# MotionerIMU.net
KiCad netlist of a schematic drawn in EAGLE
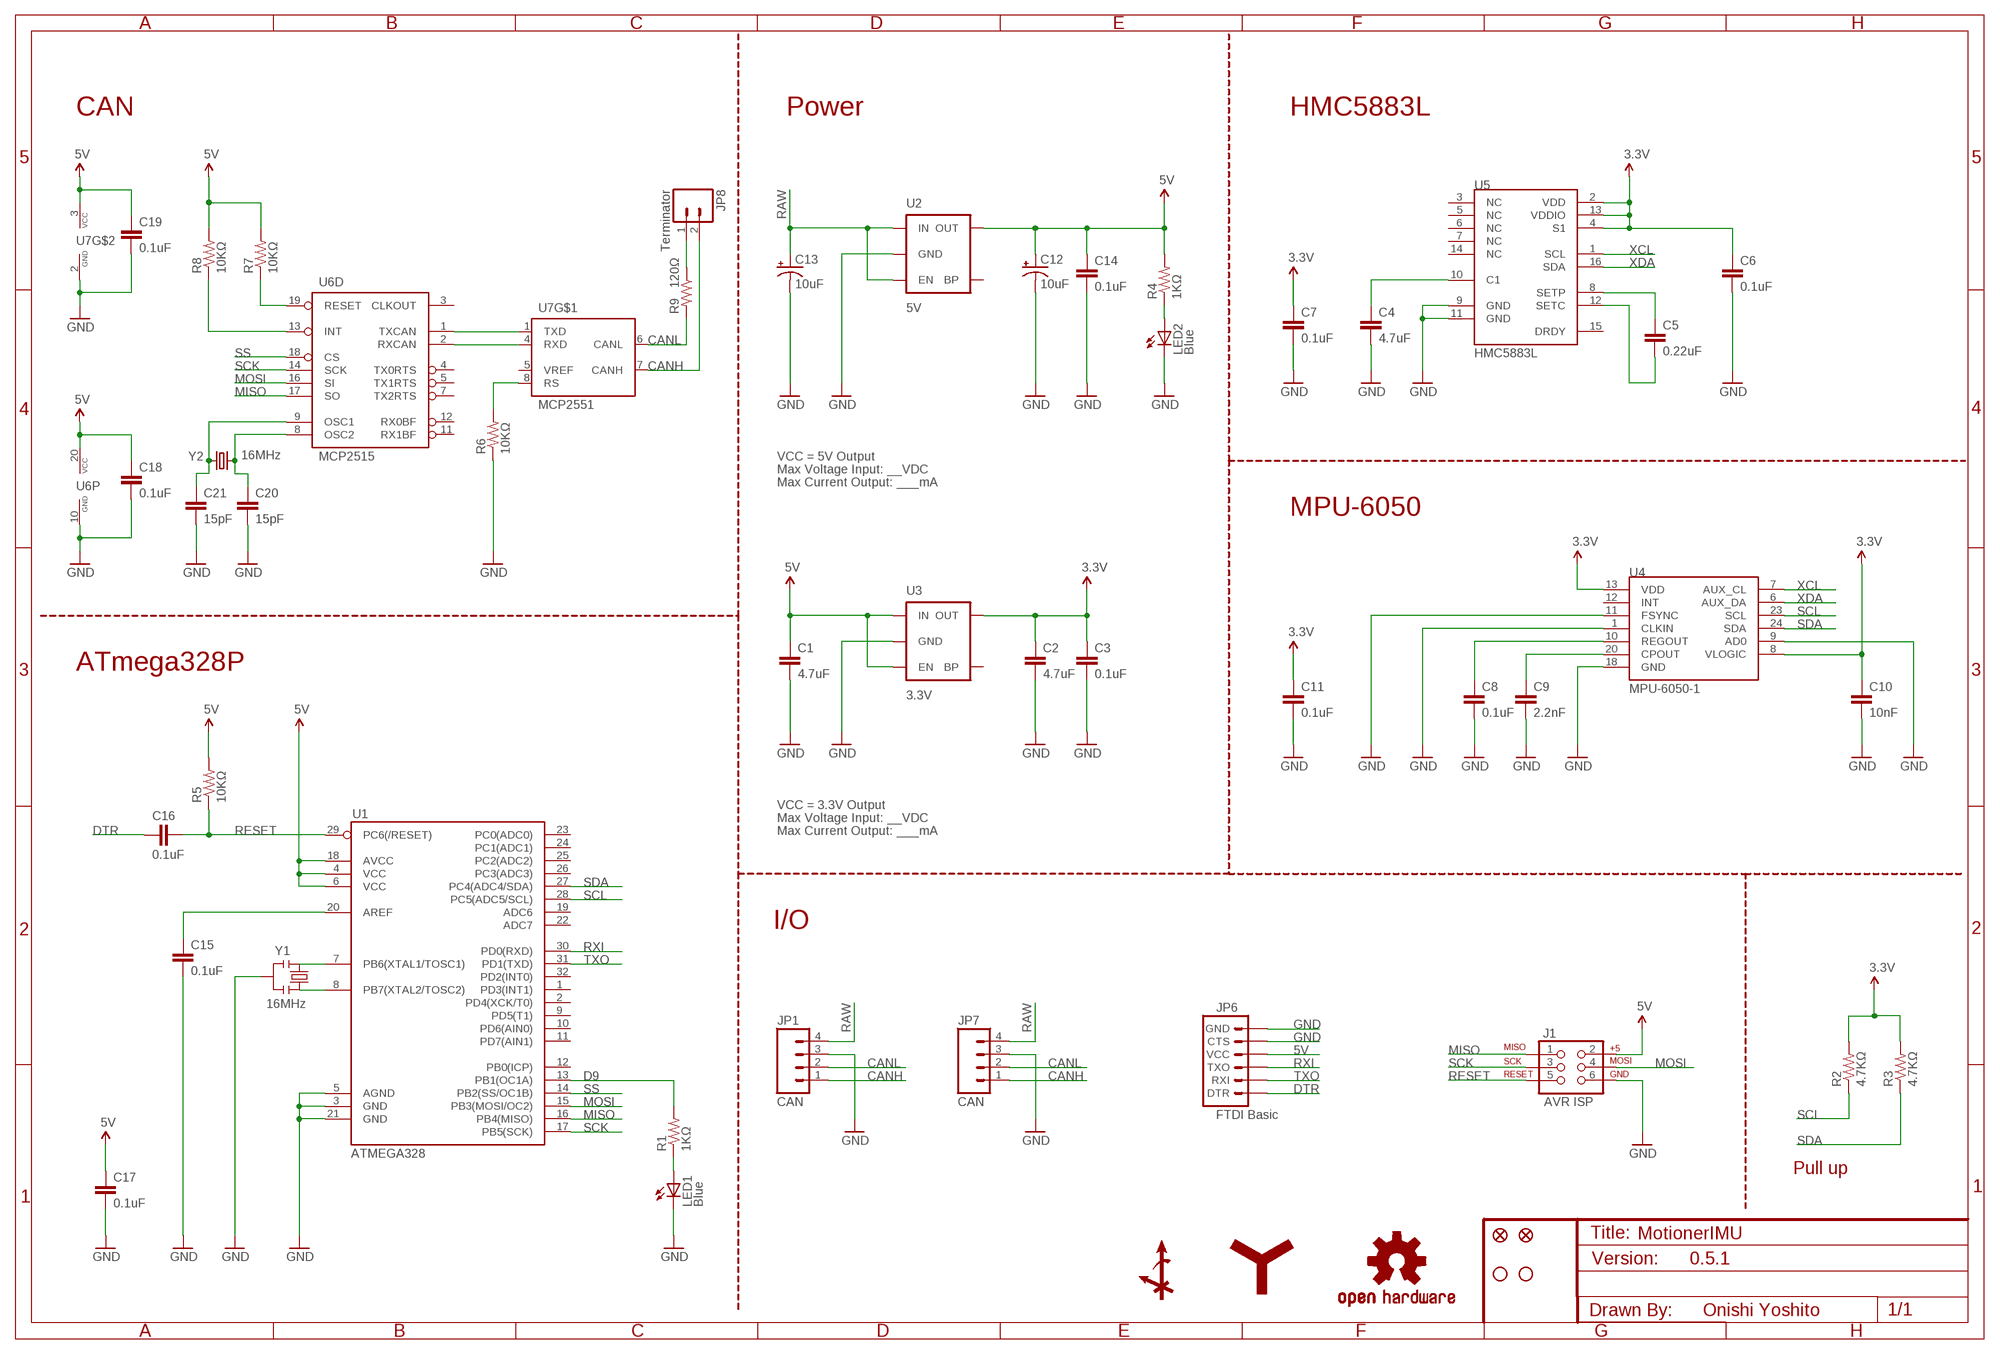
[diagram p0: schematic, sheet 1]

(export (version "E")
  (design (tool "Eeschema 10.0.6"))
  (components
    (comp (ref "C1")
      (value "4.7uF")
      (footprint "eagle-import:0402-CAP")
      (libsource (lib "eagle-import") (part "CAP0402-CAP"))
    )
    (comp (ref "C2")
      (value "4.7uF")
      (footprint "eagle-import:0402-CAP")
      (libsource (lib "eagle-import") (part "CAP0402-CAP"))
    )
    (comp (ref "C3")
      (value "0.1uF")
      (footprint "eagle-import:0402-CAP")
      (libsource (lib "eagle-import") (part "CAP0402-CAP"))
    )
    (comp (ref "C4")
      (value "4.7uF")
      (footprint "eagle-import:0402-CAP")
      (libsource (lib "eagle-import") (part "CAP0402-CAP"))
    )
    (comp (ref "C5")
      (value "0.22uF")
      (footprint "eagle-import:0402-CAP")
      (libsource (lib "eagle-import") (part "CAP0402-CAP"))
    )
    (comp (ref "C6")
      (value "0.1uF")
      (footprint "eagle-import:0402-CAP")
      (libsource (lib "eagle-import") (part "CAP0402-CAP"))
    )
    (comp (ref "C7")
      (value "0.1uF")
      (footprint "eagle-import:0402-CAP")
      (libsource (lib "eagle-import") (part "CAP0402-CAP"))
    )
    (comp (ref "C8")
      (value "0.1uF")
      (footprint "eagle-import:0402-CAP")
      (libsource (lib "eagle-import") (part "CAP0402-CAP"))
    )
    (comp (ref "C9")
      (value "2.2nF")
      (footprint "eagle-import:0402-CAP")
      (libsource (lib "eagle-import") (part "CAP0402-CAP"))
    )
    (comp (ref "C10")
      (value "10nF")
      (footprint "eagle-import:0402-CAP")
      (libsource (lib "eagle-import") (part "CAP0402-CAP"))
    )
    (comp (ref "C11")
      (value "0.1uF")
      (footprint "eagle-import:0402-CAP")
      (libsource (lib "eagle-import") (part "CAP0402-CAP"))
    )
    (comp (ref "C12")
      (value "10uF")
      (footprint "eagle-import:EIA3216")
      (libsource (lib "eagle-import") (part "CAP_POL1206"))
    )
    (comp (ref "C13")
      (value "10uF")
      (footprint "eagle-import:EIA3216")
      (libsource (lib "eagle-import") (part "CAP_POL1206"))
    )
    (comp (ref "C14")
      (value "0.1uF")
      (footprint "eagle-import:0402-CAP")
      (libsource (lib "eagle-import") (part "CAP0402-CAP"))
    )
    (comp (ref "C15")
      (value "0.1uF")
      (footprint "eagle-import:0402-CAP")
      (libsource (lib "eagle-import") (part "CAP0402-CAP"))
    )
    (comp (ref "C16")
      (value "0.1uF")
      (footprint "eagle-import:0402-CAP")
      (libsource (lib "eagle-import") (part "CAP0402-CAP"))
    )
    (comp (ref "C17")
      (value "0.1uF")
      (footprint "eagle-import:0402-CAP")
      (libsource (lib "eagle-import") (part "CAP0402-CAP"))
    )
    (comp (ref "C18")
      (value "0.1uF")
      (footprint "eagle-import:0402-CAP")
      (libsource (lib "eagle-import") (part "CAP0402-CAP"))
    )
    (comp (ref "C19")
      (value "0.1uF")
      (footprint "eagle-import:0402-CAP")
      (libsource (lib "eagle-import") (part "CAP0402-CAP"))
    )
    (comp (ref "C20")
      (value "15pF")
      (footprint "eagle-import:0402-CAP")
      (libsource (lib "eagle-import") (part "CAP0402-CAP"))
    )
    (comp (ref "C21")
      (value "15pF")
      (footprint "eagle-import:0402-CAP")
      (libsource (lib "eagle-import") (part "CAP0402-CAP"))
    )
    (comp (ref "J1")
      (value "AVR ISP")
      (footprint "eagle-import:2X3-NS")
      (libsource (lib "eagle-import") (part "AVR_SPI_PRG_6NS"))
    )
    (comp (ref "JP1")
      (value "CAN")
      (footprint "eagle-import:JST-4-PTH")
      (libsource (lib "eagle-import") (part "M04JST-PTH"))
    )
    (comp (ref "JP2")
      (value "FIDUCIALUFIDUCIAL")
      (footprint "eagle-import:MICRO-FIDUCIAL")
      (libsource (lib "eagle-import") (part "FIDUCIALUFIDUCIAL"))
    )
    (comp (ref "JP3")
      (value "STAND-OFFTIGHT")
      (footprint "eagle-import:STAND-OFF-TIGHT")
      (libsource (lib "eagle-import") (part "STAND-OFFTIGHT"))
    )
    (comp (ref "JP4")
      (value "STAND-OFFTIGHT")
      (footprint "eagle-import:STAND-OFF-TIGHT")
      (libsource (lib "eagle-import") (part "STAND-OFFTIGHT"))
    )
    (comp (ref "JP5")
      (value "FIDUCIALUFIDUCIAL")
      (footprint "eagle-import:MICRO-FIDUCIAL")
      (libsource (lib "eagle-import") (part "FIDUCIALUFIDUCIAL"))
    )
    (comp (ref "JP6")
      (value "FTDI Basic")
      (footprint "eagle-import:1X06")
      (libsource (lib "eagle-import") (part "ARDUINO_SERIAL_PROGRAMPTH"))
    )
    (comp (ref "JP7")
      (value "CAN")
      (footprint "eagle-import:JST-4-PTH")
      (libsource (lib "eagle-import") (part "M04JST-PTH"))
    )
    (comp (ref "JP8")
      (value "Terminator")
      (footprint "eagle-import:1X02")
      (libsource (lib "eagle-import") (part "M02PTH"))
    )
    (comp (ref "LED1")
      (value "Blue")
      (footprint "eagle-import:LED-0603")
      (libsource (lib "eagle-import") (part "LED0603"))
    )
    (comp (ref "LED2")
      (value "Blue")
      (footprint "eagle-import:LED-0603")
      (libsource (lib "eagle-import") (part "LED0603"))
    )
    (comp (ref "R1")
      (value "1KΩ")
      (footprint "eagle-import:0402-RES")
      (libsource (lib "eagle-import") (part "RESISTOR0402-RES"))
    )
    (comp (ref "R2")
      (value "4.7KΩ")
      (footprint "eagle-import:0402-RES")
      (libsource (lib "eagle-import") (part "RESISTOR0402-RES"))
    )
    (comp (ref "R3")
      (value "4.7KΩ")
      (footprint "eagle-import:0402-RES")
      (libsource (lib "eagle-import") (part "RESISTOR0402-RES"))
    )
    (comp (ref "R4")
      (value "1KΩ")
      (footprint "eagle-import:0402-RES")
      (libsource (lib "eagle-import") (part "RESISTOR0402-RES"))
    )
    (comp (ref "R5")
      (value "10KΩ")
      (footprint "eagle-import:0402-RES")
      (libsource (lib "eagle-import") (part "RESISTOR0402-RES"))
    )
    (comp (ref "R6")
      (value "10KΩ")
      (footprint "eagle-import:0402-RES")
      (libsource (lib "eagle-import") (part "RESISTOR0402-RES"))
    )
    (comp (ref "R7")
      (value "10KΩ")
      (footprint "eagle-import:0402-RES")
      (libsource (lib "eagle-import") (part "RESISTOR0402-RES"))
    )
    (comp (ref "R8")
      (value "10KΩ")
      (footprint "eagle-import:0402-RES")
      (libsource (lib "eagle-import") (part "RESISTOR0402-RES"))
    )
    (comp (ref "R9")
      (value "120Ω")
      (footprint "eagle-import:0402-RES")
      (libsource (lib "eagle-import") (part "RESISTOR0402-RES"))
    )
    (comp (ref "U$2")
      (value "OSHW-LOGOS")
      (footprint "eagle-import:OSHW-LOGO-S")
      (libsource (lib "eagle-import") (part "OSHW-LOGOS"))
    )
    (comp (ref "U$11")
      (value "AXIS-ANGLE_S")
      (footprint "eagle-import:AXIS-ANGLE_S")
      (libsource (lib "eagle-import") (part "AXIS-ANGLE_S"))
    )
    (comp (ref "U$13")
      (value "YCAM_LOGO_L")
      (footprint "eagle-import:YCAM_LOGO_L")
      (libsource (lib "eagle-import") (part "YCAM_LOGO_L"))
    )
    (comp (ref "U1")
      (value "ATMEGA328")
      (footprint "eagle-import:TQFP32-08")
      (libsource (lib "eagle-import") (part "ATMEGA168"))
    )
    (comp (ref "U2")
      (value "5V")
      (footprint "eagle-import:SOT23-5")
      (libsource (lib "eagle-import") (part "V_REG_LDOSMD"))
    )
    (comp (ref "U3")
      (value "3.3V")
      (footprint "eagle-import:SOT23-5")
      (libsource (lib "eagle-import") (part "V_REG_LDOSMD"))
    )
    (comp (ref "U4")
      (value "MPU-6050-1")
      (footprint "eagle-import:QFN-24-4MM2")
      (libsource (lib "eagle-import") (part "MPU-6050-1"))
    )
    (comp (ref "U5")
      (value "HMC5883L")
      (footprint "eagle-import:16LPCC")
      (libsource (lib "eagle-import") (part "HMC5883LSMD"))
    )
    (comp (ref "U6")
      (value "MCP2515")
      (footprint "eagle-import:TSSOP20")
      (libsource (lib "eagle-import") (part "MCP2515ST"))
    )
    (comp (ref "U7")
      (value "MCP2551")
      (footprint "eagle-import:SO08")
      (libsource (lib "eagle-import") (part "MCP2551SO8"))
    )
    (comp (ref "Y1")
      (value "16MHz")
      (footprint "eagle-import:RESONATOR-SMD")
      (libsource (lib "eagle-import") (part "RESONATORSMD"))
    )
    (comp (ref "Y2")
      (value "16MHz")
      (footprint "eagle-import:CRYSTAL-SMD-5X3")
      (libsource (lib "eagle-import") (part "CRYSTAL5X3"))
    )
  )
  (nets
    (net (code "1") (name "/CANH") (class "Default")
      (node (ref "JP1") (pin "1") (pinfunction "1_1") (pintype "passive"))
      (node (ref "JP7") (pin "1") (pinfunction "1_1") (pintype "passive"))
      (node (ref "JP8") (pin "2") (pinfunction "2_2") (pintype "passive"))
      (node (ref "U7") (pin "7") (pinfunction "CANH_7") (pintype "bidirectional"))
    )
    (net (code "2") (name "/CANL") (class "Default")
      (node (ref "JP1") (pin "2") (pinfunction "2_2") (pintype "passive"))
      (node (ref "JP7") (pin "2") (pinfunction "2_2") (pintype "passive"))
      (node (ref "R9") (pin "2") (pinfunction "2_2") (pintype "passive"))
      (node (ref "U7") (pin "6") (pinfunction "CANL_6") (pintype "bidirectional"))
    )
    (net (code "3") (name "/D9") (class "Default")
      (node (ref "R1") (pin "2") (pinfunction "2_2") (pintype "passive"))
      (node (ref "U1") (pin "13") (pinfunction "PB1(OC1A)_13") (pintype "bidirectional"))
    )
    (net (code "4") (name "/DTR") (class "Default")
      (node (ref "C16") (pin "1") (pinfunction "1_1") (pintype "passive"))
      (node (ref "JP6") (pin "1") (pinfunction "DTR_1") (pintype "passive"))
    )
    (net (code "5") (name "/MISO") (class "Default")
      (node (ref "J1") (pin "1") (pinfunction "1_1") (pintype "passive"))
      (node (ref "U1") (pin "16") (pinfunction "PB4(MISO)_16") (pintype "bidirectional"))
      (node (ref "U6") (pin "17") (pinfunction "SO_17") (pintype "output"))
    )
    (net (code "6") (name "/MOSI") (class "Default")
      (node (ref "J1") (pin "4") (pinfunction "4_4") (pintype "passive"))
      (node (ref "U1") (pin "15") (pinfunction "PB3(MOSI/OC2)_15") (pintype "bidirectional"))
      (node (ref "U6") (pin "16") (pinfunction "SI_16") (pintype "input"))
    )
    (net (code "7") (name "/RAW") (class "Default")
      (node (ref "C13") (pin "A") (pinfunction "+_A") (pintype "passive"))
      (node (ref "JP1") (pin "4") (pinfunction "4_4") (pintype "passive"))
      (node (ref "JP7") (pin "4") (pinfunction "4_4") (pintype "passive"))
      (node (ref "U2") (pin "1") (pinfunction "IN_1") (pintype "input"))
      (node (ref "U2") (pin "3") (pinfunction "EN_3") (pintype "input"))
    )
    (net (code "8") (name "/RESET") (class "Default")
      (node (ref "C16") (pin "2") (pinfunction "2_2") (pintype "passive"))
      (node (ref "J1") (pin "5") (pinfunction "5_5") (pintype "passive"))
      (node (ref "R5") (pin "1") (pinfunction "1_1") (pintype "passive"))
      (node (ref "U1") (pin "29") (pinfunction "PC6(/RESET)_29") (pintype "bidirectional"))
    )
    (net (code "9") (name "/RXI") (class "Default")
      (node (ref "JP6") (pin "3") (pinfunction "TXO_3") (pintype "passive"))
      (node (ref "U1") (pin "30") (pinfunction "PD0(RXD)_30") (pintype "bidirectional"))
    )
    (net (code "10") (name "/SCK") (class "Default")
      (node (ref "J1") (pin "3") (pinfunction "3_3") (pintype "passive"))
      (node (ref "U1") (pin "17") (pinfunction "PB5(SCK)_17") (pintype "bidirectional"))
      (node (ref "U6") (pin "14") (pinfunction "SCK_14") (pintype "input"))
    )
    (net (code "11") (name "/SCL") (class "Default")
      (node (ref "R2") (pin "1") (pinfunction "1_1") (pintype "passive"))
      (node (ref "U1") (pin "28") (pinfunction "PC5(ADC5/SCL)_28") (pintype "bidirectional"))
      (node (ref "U4") (pin "23") (pinfunction "SCL_23") (pintype "bidirectional"))
    )
    (net (code "12") (name "/SDA") (class "Default")
      (node (ref "R3") (pin "1") (pinfunction "1_1") (pintype "passive"))
      (node (ref "U1") (pin "27") (pinfunction "PC4(ADC4/SDA)_27") (pintype "bidirectional"))
      (node (ref "U4") (pin "24") (pinfunction "SDA_24") (pintype "bidirectional"))
    )
    (net (code "13") (name "/SS") (class "Default")
      (node (ref "U1") (pin "14") (pinfunction "PB2(SS/OC1B)_14") (pintype "bidirectional"))
      (node (ref "U6") (pin "18") (pinfunction "CS_18") (pintype "input"))
    )
    (net (code "14") (name "/TXO") (class "Default")
      (node (ref "JP6") (pin "2") (pinfunction "RXI_2") (pintype "passive"))
      (node (ref "U1") (pin "31") (pinfunction "PD1(TXD)_31") (pintype "bidirectional"))
    )
    (net (code "15") (name "/XCL") (class "Default")
      (node (ref "U4") (pin "7") (pinfunction "AUX_CL_7") (pintype "bidirectional"))
      (node (ref "U5") (pin "1") (pinfunction "SCL_1") (pintype "bidirectional"))
    )
    (net (code "16") (name "/XDA") (class "Default")
      (node (ref "U4") (pin "6") (pinfunction "AUX_DA_6") (pintype "bidirectional"))
      (node (ref "U5") (pin "16") (pinfunction "SDA_16") (pintype "bidirectional"))
    )
    (net (code "17") (name "3.3V") (class "Default")
      (node (ref "C10") (pin "1") (pinfunction "1_1") (pintype "passive"))
      (node (ref "C11") (pin "1") (pinfunction "1_1") (pintype "passive"))
      (node (ref "C2") (pin "1") (pinfunction "1_1") (pintype "passive"))
      (node (ref "C3") (pin "1") (pinfunction "1_1") (pintype "passive"))
      (node (ref "C6") (pin "1") (pinfunction "1_1") (pintype "passive"))
      (node (ref "C7") (pin "1") (pinfunction "1_1") (pintype "passive"))
      (node (ref "R2") (pin "2") (pinfunction "2_2") (pintype "passive"))
      (node (ref "R3") (pin "2") (pinfunction "2_2") (pintype "passive"))
      (node (ref "U3") (pin "5") (pinfunction "OUT_5") (pintype "passive"))
      (node (ref "U4") (pin "13") (pinfunction "VDD_13") (pintype "bidirectional"))
      (node (ref "U4") (pin "8") (pinfunction "VLOGIC_8") (pintype "bidirectional"))
      (node (ref "U5") (pin "13") (pinfunction "VDDIO_13") (pintype "bidirectional"))
      (node (ref "U5") (pin "2") (pinfunction "VDD_2") (pintype "bidirectional"))
      (node (ref "U5") (pin "4") (pinfunction "S1_4") (pintype "bidirectional"))
    )
    (net (code "18") (name "5V") (class "Default")
      (node (ref "C1") (pin "1") (pinfunction "1_1") (pintype "passive"))
      (node (ref "C12") (pin "A") (pinfunction "+_A") (pintype "passive"))
      (node (ref "C14") (pin "1") (pinfunction "1_1") (pintype "passive"))
      (node (ref "C17") (pin "1") (pinfunction "1_1") (pintype "passive"))
      (node (ref "C18") (pin "1") (pinfunction "1_1") (pintype "passive"))
      (node (ref "C19") (pin "1") (pinfunction "1_1") (pintype "passive"))
      (node (ref "J1") (pin "2") (pinfunction "2_2") (pintype "passive"))
      (node (ref "JP6") (pin "4") (pinfunction "VCC_4") (pintype "passive"))
      (node (ref "R4") (pin "2") (pinfunction "2_2") (pintype "passive"))
      (node (ref "R5") (pin "2") (pinfunction "2_2") (pintype "passive"))
      (node (ref "R7") (pin "2") (pinfunction "2_2") (pintype "passive"))
      (node (ref "R8") (pin "2") (pinfunction "2_2") (pintype "passive"))
      (node (ref "U1") (pin "18") (pinfunction "AVCC_18") (pintype "bidirectional"))
      (node (ref "U1") (pin "4") (pinfunction "VCC_4") (pintype "bidirectional"))
      (node (ref "U1") (pin "6") (pinfunction "VCC_6") (pintype "bidirectional"))
      (node (ref "U2") (pin "5") (pinfunction "OUT_5") (pintype "passive"))
      (node (ref "U3") (pin "1") (pinfunction "IN_1") (pintype "input"))
      (node (ref "U3") (pin "3") (pinfunction "EN_3") (pintype "input"))
      (node (ref "U6") (pin "20") (pinfunction "VCC_20") (pintype "power_in"))
      (node (ref "U7") (pin "3") (pinfunction "VCC_3") (pintype "power_in"))
    )
    (net (code "19") (name "GND") (class "Default")
      (node (ref "C1") (pin "2") (pinfunction "2_2") (pintype "passive"))
      (node (ref "C10") (pin "2") (pinfunction "2_2") (pintype "passive"))
      (node (ref "C11") (pin "2") (pinfunction "2_2") (pintype "passive"))
      (node (ref "C12") (pin "C") (pinfunction "-_C") (pintype "passive"))
      (node (ref "C13") (pin "C") (pinfunction "-_C") (pintype "passive"))
      (node (ref "C14") (pin "2") (pinfunction "2_2") (pintype "passive"))
      (node (ref "C15") (pin "2") (pinfunction "2_2") (pintype "passive"))
      (node (ref "C17") (pin "2") (pinfunction "2_2") (pintype "passive"))
      (node (ref "C18") (pin "2") (pinfunction "2_2") (pintype "passive"))
      (node (ref "C19") (pin "2") (pinfunction "2_2") (pintype "passive"))
      (node (ref "C2") (pin "2") (pinfunction "2_2") (pintype "passive"))
      (node (ref "C20") (pin "2") (pinfunction "2_2") (pintype "passive"))
      (node (ref "C21") (pin "2") (pinfunction "2_2") (pintype "passive"))
      (node (ref "C3") (pin "2") (pinfunction "2_2") (pintype "passive"))
      (node (ref "C4") (pin "2") (pinfunction "2_2") (pintype "passive"))
      (node (ref "C6") (pin "2") (pinfunction "2_2") (pintype "passive"))
      (node (ref "C7") (pin "2") (pinfunction "2_2") (pintype "passive"))
      (node (ref "C8") (pin "2") (pinfunction "2_2") (pintype "passive"))
      (node (ref "C9") (pin "2") (pinfunction "2_2") (pintype "passive"))
      (node (ref "J1") (pin "6") (pinfunction "6_6") (pintype "passive"))
      (node (ref "JP1") (pin "3") (pinfunction "3_3") (pintype "passive"))
      (node (ref "JP6") (pin "5") (pinfunction "CTS_5") (pintype "passive"))
      (node (ref "JP6") (pin "6") (pinfunction "GND_6") (pintype "passive"))
      (node (ref "JP7") (pin "3") (pinfunction "3_3") (pintype "passive"))
      (node (ref "LED1") (pin "C") (pinfunction "C_C") (pintype "passive"))
      (node (ref "LED2") (pin "C") (pinfunction "C_C") (pintype "passive"))
      (node (ref "R6") (pin "1") (pinfunction "1_1") (pintype "passive"))
      (node (ref "U1") (pin "21") (pinfunction "GND_21") (pintype "bidirectional"))
      (node (ref "U1") (pin "3") (pinfunction "GND_3") (pintype "bidirectional"))
      (node (ref "U1") (pin "5") (pinfunction "AGND_5") (pintype "bidirectional"))
      (node (ref "U2") (pin "2") (pinfunction "GND_2") (pintype "input"))
      (node (ref "U3") (pin "2") (pinfunction "GND_2") (pintype "input"))
      (node (ref "U4") (pin "1") (pinfunction "CLKIN_1") (pintype "bidirectional"))
      (node (ref "U4") (pin "11") (pinfunction "FSYNC_11") (pintype "bidirectional"))
      (node (ref "U4") (pin "18") (pinfunction "GND_18") (pintype "bidirectional"))
      (node (ref "U4") (pin "9") (pinfunction "AD0_9") (pintype "bidirectional"))
      (node (ref "U5") (pin "11") (pinfunction "GND_11") (pintype "bidirectional"))
      (node (ref "U5") (pin "9") (pinfunction "GND_9") (pintype "bidirectional"))
      (node (ref "U6") (pin "10") (pinfunction "GND_10") (pintype "power_in"))
      (node (ref "U7") (pin "2") (pinfunction "GND_2") (pintype "power_in"))
      (node (ref "Y1") (pin "2") (pinfunction "2_2") (pintype "passive"))
    )
    (net (code "20") (name "Net-(JP8-Pad1)") (class "Default")
      (node (ref "JP8") (pin "1") (pinfunction "1_1") (pintype "passive"))
      (node (ref "R9") (pin "1") (pinfunction "1_1") (pintype "passive"))
    )
    (net (code "21") (name "Net-(LED1-PadA)") (class "Default")
      (node (ref "LED1") (pin "A") (pinfunction "A_A") (pintype "passive"))
      (node (ref "R1") (pin "1") (pinfunction "1_1") (pintype "passive"))
    )
    (net (code "22") (name "Net-(LED2-PadA)") (class "Default")
      (node (ref "LED2") (pin "A") (pinfunction "A_A") (pintype "passive"))
      (node (ref "R4") (pin "1") (pinfunction "1_1") (pintype "passive"))
    )
    (net (code "23") (name "Net-(U1-AREF)") (class "Default")
      (node (ref "C15") (pin "1") (pinfunction "1_1") (pintype "passive"))
      (node (ref "U1") (pin "20") (pinfunction "AREF_20") (pintype "bidirectional"))
    )
    (net (code "24") (name "Net-(U1-PB6(XTAL1{slash}TOSC1))") (class "Default")
      (node (ref "U1") (pin "7") (pinfunction "PB6(XTAL1/TOSC1)_7") (pintype "bidirectional"))
      (node (ref "Y1") (pin "1") (pinfunction "1_1") (pintype "passive"))
    )
    (net (code "25") (name "Net-(U1-PB7(XTAL2{slash}TOSC2))") (class "Default")
      (node (ref "U1") (pin "8") (pinfunction "PB7(XTAL2/TOSC2)_8") (pintype "bidirectional"))
      (node (ref "Y1") (pin "3") (pinfunction "3_3") (pintype "passive"))
    )
    (net (code "26") (name "Net-(U4-CPOUT)") (class "Default")
      (node (ref "C9") (pin "1") (pinfunction "1_1") (pintype "passive"))
      (node (ref "U4") (pin "20") (pinfunction "CPOUT_20") (pintype "bidirectional"))
    )
    (net (code "27") (name "Net-(U4-REGOUT)") (class "Default")
      (node (ref "C8") (pin "1") (pinfunction "1_1") (pintype "passive"))
      (node (ref "U4") (pin "10") (pinfunction "REGOUT_10") (pintype "bidirectional"))
    )
    (net (code "28") (name "Net-(U5-C1)") (class "Default")
      (node (ref "C4") (pin "1") (pinfunction "1_1") (pintype "passive"))
      (node (ref "U5") (pin "10") (pinfunction "C1_10") (pintype "bidirectional"))
    )
    (net (code "29") (name "Net-(U5-SETC)") (class "Default")
      (node (ref "C5") (pin "2") (pinfunction "2_2") (pintype "passive"))
      (node (ref "U5") (pin "12") (pinfunction "SETC_12") (pintype "bidirectional"))
    )
    (net (code "30") (name "Net-(U5-SETP)") (class "Default")
      (node (ref "C5") (pin "1") (pinfunction "1_1") (pintype "passive"))
      (node (ref "U5") (pin "8") (pinfunction "SETP_8") (pintype "bidirectional"))
    )
    (net (code "31") (name "Net-(U6A-INT)") (class "Default")
      (node (ref "R8") (pin "1") (pinfunction "1_1") (pintype "passive"))
      (node (ref "U6") (pin "13") (pinfunction "INT_13") (pintype "output"))
    )
    (net (code "32") (name "Net-(U6A-OSC1)") (class "Default")
      (node (ref "C21") (pin "1") (pinfunction "1_1") (pintype "passive"))
      (node (ref "U6") (pin "9") (pinfunction "OSC1_9") (pintype "input"))
      (node (ref "Y2") (pin "1") (pinfunction "1_1") (pintype "passive"))
    )
    (net (code "33") (name "Net-(U6A-OSC2)") (class "Default")
      (node (ref "C20") (pin "1") (pinfunction "1_1") (pintype "passive"))
      (node (ref "U6") (pin "8") (pinfunction "OSC2_8") (pintype "input"))
      (node (ref "Y2") (pin "3") (pinfunction "2_3") (pintype "passive"))
    )
    (net (code "34") (name "Net-(U6A-RESET)") (class "Default")
      (node (ref "R7") (pin "1") (pinfunction "1_1") (pintype "passive"))
      (node (ref "U6") (pin "19") (pinfunction "RESET_19") (pintype "input"))
    )
    (net (code "35") (name "Net-(U6A-RXCAN)") (class "Default")
      (node (ref "U6") (pin "2") (pinfunction "RXCAN_2") (pintype "input"))
      (node (ref "U7") (pin "4") (pinfunction "RXD_4") (pintype "bidirectional"))
    )
    (net (code "36") (name "Net-(U6A-TXCAN)") (class "Default")
      (node (ref "U6") (pin "1") (pinfunction "TXCAN_1") (pintype "output"))
      (node (ref "U7") (pin "1") (pinfunction "TXD_1") (pintype "bidirectional"))
    )
    (net (code "37") (name "Net-(U7A-RS)") (class "Default")
      (node (ref "R6") (pin "2") (pinfunction "2_2") (pintype "passive"))
      (node (ref "U7") (pin "8") (pinfunction "RS_8") (pintype "bidirectional"))
    )
    (net (code "38") (name "unconnected-(U1-ADC6-Pad19)") (class "Default")
      (node (ref "U1") (pin "19") (pinfunction "ADC6_19") (pintype "bidirectional"))
    )
    (net (code "39") (name "unconnected-(U1-ADC7-Pad22)") (class "Default")
      (node (ref "U1") (pin "22") (pinfunction "ADC7_22") (pintype "bidirectional"))
    )
    (net (code "40") (name "unconnected-(U1-PB0(ICP)-Pad12)") (class "Default")
      (node (ref "U1") (pin "12") (pinfunction "PB0(ICP)_12") (pintype "bidirectional"))
    )
    (net (code "41") (name "unconnected-(U1-PC0(ADC0)-Pad23)") (class "Default")
      (node (ref "U1") (pin "23") (pinfunction "PC0(ADC0)_23") (pintype "bidirectional"))
    )
    (net (code "42") (name "unconnected-(U1-PC1(ADC1)-Pad24)") (class "Default")
      (node (ref "U1") (pin "24") (pinfunction "PC1(ADC1)_24") (pintype "bidirectional"))
    )
    (net (code "43") (name "unconnected-(U1-PC2(ADC2)-Pad25)") (class "Default")
      (node (ref "U1") (pin "25") (pinfunction "PC2(ADC2)_25") (pintype "bidirectional"))
    )
    (net (code "44") (name "unconnected-(U1-PC3(ADC3)-Pad26)") (class "Default")
      (node (ref "U1") (pin "26") (pinfunction "PC3(ADC3)_26") (pintype "bidirectional"))
    )
    (net (code "45") (name "unconnected-(U1-PD2(INT0)-Pad32)") (class "Default")
      (node (ref "U1") (pin "32") (pinfunction "PD2(INT0)_32") (pintype "bidirectional"))
    )
    (net (code "46") (name "unconnected-(U1-PD3(INT1)-Pad1)") (class "Default")
      (node (ref "U1") (pin "1") (pinfunction "PD3(INT1)_1") (pintype "bidirectional"))
    )
    (net (code "47") (name "unconnected-(U1-PD4(XCK{slash}T0)-Pad2)") (class "Default")
      (node (ref "U1") (pin "2") (pinfunction "PD4(XCK/T0)_2") (pintype "bidirectional"))
    )
    (net (code "48") (name "unconnected-(U1-PD5(T1)-Pad9)") (class "Default")
      (node (ref "U1") (pin "9") (pinfunction "PD5(T1)_9") (pintype "bidirectional"))
    )
    (net (code "49") (name "unconnected-(U1-PD6(AIN0)-Pad10)") (class "Default")
      (node (ref "U1") (pin "10") (pinfunction "PD6(AIN0)_10") (pintype "bidirectional"))
    )
    (net (code "50") (name "unconnected-(U1-PD7(AIN1)-Pad11)") (class "Default")
      (node (ref "U1") (pin "11") (pinfunction "PD7(AIN1)_11") (pintype "bidirectional"))
    )
    (net (code "51") (name "unconnected-(U2-BP-Pad4)") (class "Default")
      (node (ref "U2") (pin "4") (pinfunction "BP_4") (pintype "input"))
    )
    (net (code "52") (name "unconnected-(U3-BP-Pad4)") (class "Default")
      (node (ref "U3") (pin "4") (pinfunction "BP_4") (pintype "input"))
    )
    (net (code "53") (name "unconnected-(U4-INT-Pad12)") (class "Default")
      (node (ref "U4") (pin "12") (pinfunction "INT_12") (pintype "bidirectional"))
    )
    (net (code "54") (name "unconnected-(U5-DRDY-Pad15)") (class "Default")
      (node (ref "U5") (pin "15") (pinfunction "DRDY_15") (pintype "bidirectional"))
    )
    (net (code "55") (name "unconnected-(U5-NC-Pad3)") (class "Default")
      (node (ref "U5") (pin "3") (pinfunction "NC_3") (pintype "bidirectional"))
    )
    (net (code "56") (name "unconnected-(U5-NC-Pad5)") (class "Default")
      (node (ref "U5") (pin "5") (pinfunction "NC_5") (pintype "bidirectional"))
    )
    (net (code "57") (name "unconnected-(U5-NC-Pad6)") (class "Default")
      (node (ref "U5") (pin "6") (pinfunction "NC_6") (pintype "bidirectional"))
    )
    (net (code "58") (name "unconnected-(U5-NC-Pad7)") (class "Default")
      (node (ref "U5") (pin "7") (pinfunction "NC_7") (pintype "bidirectional"))
    )
    (net (code "59") (name "unconnected-(U5-NC-Pad14)") (class "Default")
      (node (ref "U5") (pin "14") (pinfunction "NC_14") (pintype "bidirectional"))
    )
    (net (code "60") (name "unconnected-(U6A-CLKOUT-Pad3)") (class "Default")
      (node (ref "U6") (pin "3") (pinfunction "CLKOUT_3") (pintype "output"))
    )
    (net (code "61") (name "unconnected-(U6A-RX0BF-Pad12)") (class "Default")
      (node (ref "U6") (pin "12") (pinfunction "RX0BF_12") (pintype "output"))
    )
    (net (code "62") (name "unconnected-(U6A-RX1BF-Pad11)") (class "Default")
      (node (ref "U6") (pin "11") (pinfunction "RX1BF_11") (pintype "output"))
    )
    (net (code "63") (name "unconnected-(U6A-TX0RTS-Pad4)") (class "Default")
      (node (ref "U6") (pin "4") (pinfunction "TX0RTS_4") (pintype "input"))
    )
    (net (code "64") (name "unconnected-(U6A-TX1RTS-Pad5)") (class "Default")
      (node (ref "U6") (pin "5") (pinfunction "TX1RTS_5") (pintype "input"))
    )
    (net (code "65") (name "unconnected-(U6A-TX2RTS-Pad7)") (class "Default")
      (node (ref "U6") (pin "7") (pinfunction "TX2RTS_7") (pintype "input"))
    )
    (net (code "66") (name "unconnected-(U7A-VREF-Pad5)") (class "Default")
      (node (ref "U7") (pin "5") (pinfunction "VREF_5") (pintype "bidirectional"))
    )
  )
)
